# AguaC.net
KiCad netlist of a schematic drawn in EAGLE
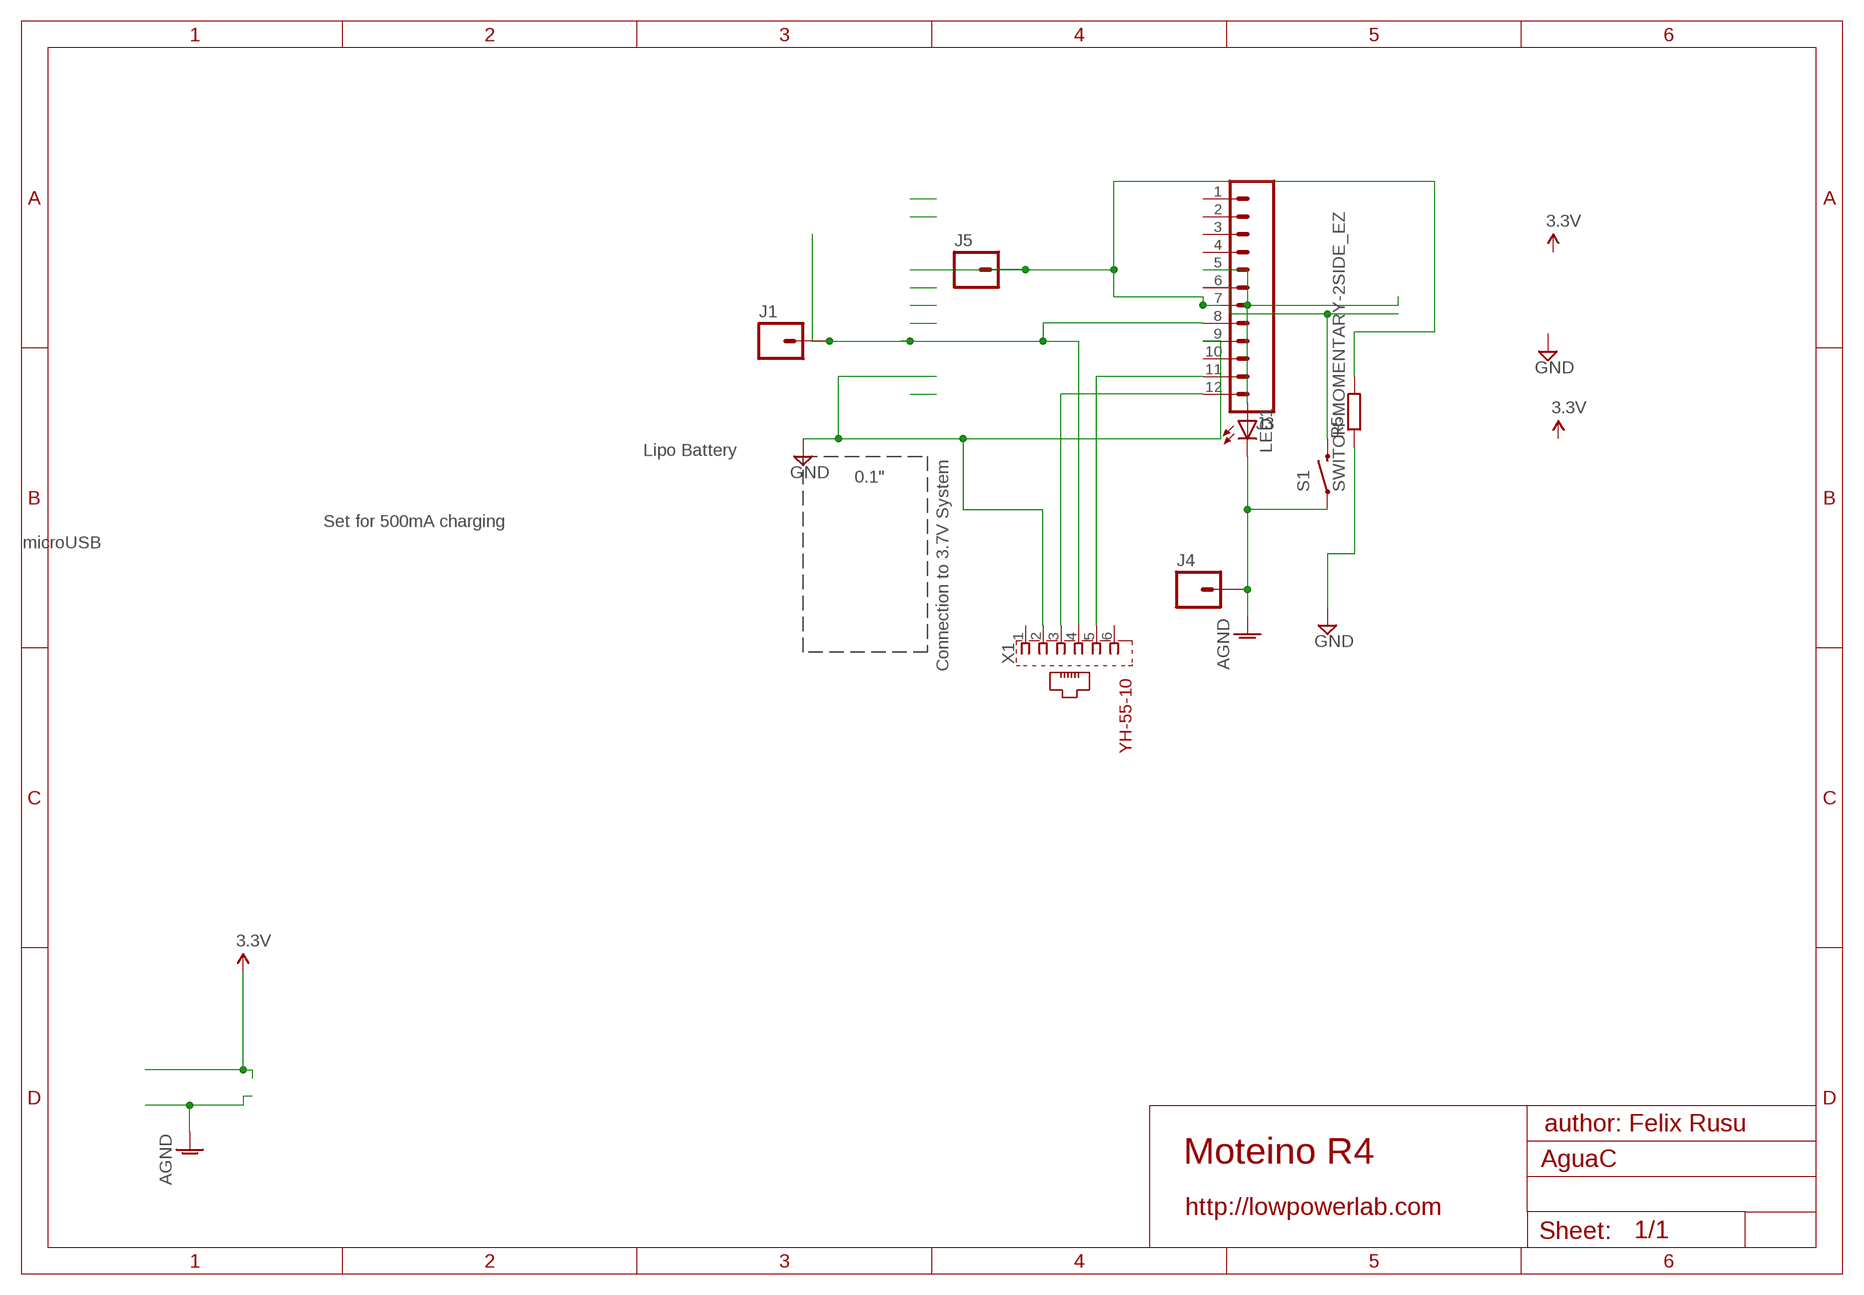
[diagram p0: schematic, sheet 1]

(export (version "E")
  (design (tool "Eeschema 10.0.6"))
  (components
    (comp (ref "J1")
      (value "M01PTH")
      (footprint "eagle-import:1X01")
      (libsource (lib "eagle-import") (part "M01PTH"))
    )
    (comp (ref "J3")
      (value "M12PTH")
      (footprint "eagle-import:1X12")
      (libsource (lib "eagle-import") (part "M12PTH"))
    )
    (comp (ref "J4")
      (value "M01PTH")
      (footprint "eagle-import:1X01")
      (libsource (lib "eagle-import") (part "M01PTH"))
    )
    (comp (ref "J5")
      (value "M01PTH")
      (footprint "eagle-import:1X01")
      (libsource (lib "eagle-import") (part "M01PTH"))
    )
    (comp (ref "LED1")
      (value "LED3MM")
      (footprint "eagle-import:LED3MM")
      (libsource (lib "eagle-import") (part "LED3MM"))
    )
    (comp (ref "R5")
      (value "R-EU_0204/7")
      (footprint "eagle-import:0204_7")
      (libsource (lib "eagle-import") (part "R-EU_0204/7"))
    )
    (comp (ref "S1")
      (value "SWITCH-MOMENTARY-2SIDE_EZ")
      (footprint "eagle-import:TACTILE-PTH-SIDEEZ")
      (libsource (lib "eagle-import") (part "SWITCH-MOMENTARY-2SIDE_EZ"))
    )
    (comp (ref "X1")
      (value "YH-55-10")
      (footprint "eagle-import:YH-55-10")
      (libsource (lib "eagle-import") (part "YH-55-10"))
    )
  )
  (nets
    (net (code "2") (name "AGND") (class "Default")
      (node (ref "J4") (pin "1") (pinfunction "1_1") (pintype "passive"))
      (node (ref "LED1") (pin "K") (pinfunction "C_K") (pintype "passive"))
      (node (ref "S1") (pin "1") (pinfunction "1_1") (pintype "passive"))
    )
    (net (code "3") (name "GND") (class "Default")
      (node (ref "J3") (pin "9") (pinfunction "9_9") (pintype "passive"))
      (node (ref "R5") (pin "1") (pinfunction "1_1") (pintype "passive"))
      (node (ref "X1") (pin "2") (pinfunction "2_2") (pintype "passive"))
    )
    (net (code "4") (name "Net-(J1-Pad1)") (class "Default")
      (node (ref "J1") (pin "1") (pinfunction "1_1") (pintype "passive"))
      (node (ref "J3") (pin "8") (pinfunction "8_8") (pintype "passive"))
      (node (ref "X1") (pin "4") (pinfunction "4_4") (pintype "passive"))
    )
    (net (code "5") (name "Net-(J3-Pad5)") (class "Default")
      (node (ref "J3") (pin "5") (pinfunction "5_5") (pintype "passive"))
      (node (ref "LED1") (pin "A") (pinfunction "A_A") (pintype "passive"))
    )
    (net (code "6") (name "Net-(J3-Pad6)") (class "Default")
      (node (ref "J3") (pin "6") (pinfunction "6_6") (pintype "passive"))
      (node (ref "S1") (pin "2") (pinfunction "2_2") (pintype "passive"))
    )
    (net (code "7") (name "Net-(J3-Pad7)") (class "Default")
      (node (ref "J3") (pin "7") (pinfunction "7_7") (pintype "passive"))
      (node (ref "J5") (pin "1") (pinfunction "1_1") (pintype "passive"))
      (node (ref "R5") (pin "2") (pinfunction "2_2") (pintype "passive"))
    )
    (net (code "8") (name "Net-(J3-Pad11)") (class "Default")
      (node (ref "J3") (pin "11") (pinfunction "11_11") (pintype "passive"))
      (node (ref "X1") (pin "5") (pinfunction "5_5") (pintype "passive"))
    )
    (net (code "9") (name "Net-(J3-Pad12)") (class "Default")
      (node (ref "J3") (pin "12") (pinfunction "12_12") (pintype "passive"))
      (node (ref "X1") (pin "3") (pinfunction "3_3") (pintype "passive"))
    )
    (net (code "10") (name "unconnected-(J3-Pad1)") (class "Default")
      (node (ref "J3") (pin "1") (pinfunction "1_1") (pintype "passive"))
    )
    (net (code "11") (name "unconnected-(J3-Pad2)") (class "Default")
      (node (ref "J3") (pin "2") (pinfunction "2_2") (pintype "passive"))
    )
    (net (code "12") (name "unconnected-(J3-Pad3)") (class "Default")
      (node (ref "J3") (pin "3") (pinfunction "3_3") (pintype "passive"))
    )
    (net (code "13") (name "unconnected-(J3-Pad4)") (class "Default")
      (node (ref "J3") (pin "4") (pinfunction "4_4") (pintype "passive"))
    )
    (net (code "14") (name "unconnected-(J3-Pad10)") (class "Default")
      (node (ref "J3") (pin "10") (pinfunction "10_10") (pintype "passive"))
    )
    (net (code "15") (name "unconnected-(X1-Pad1)") (class "Default")
      (node (ref "X1") (pin "1") (pinfunction "1_1") (pintype "passive"))
    )
    (net (code "16") (name "unconnected-(X1-Pad6)") (class "Default")
      (node (ref "X1") (pin "6") (pinfunction "6_6") (pintype "passive"))
    )
  )
)
